# EN-C200-OPT_RA1.net
KiCad netlist of a schematic drawn in Altium Designer
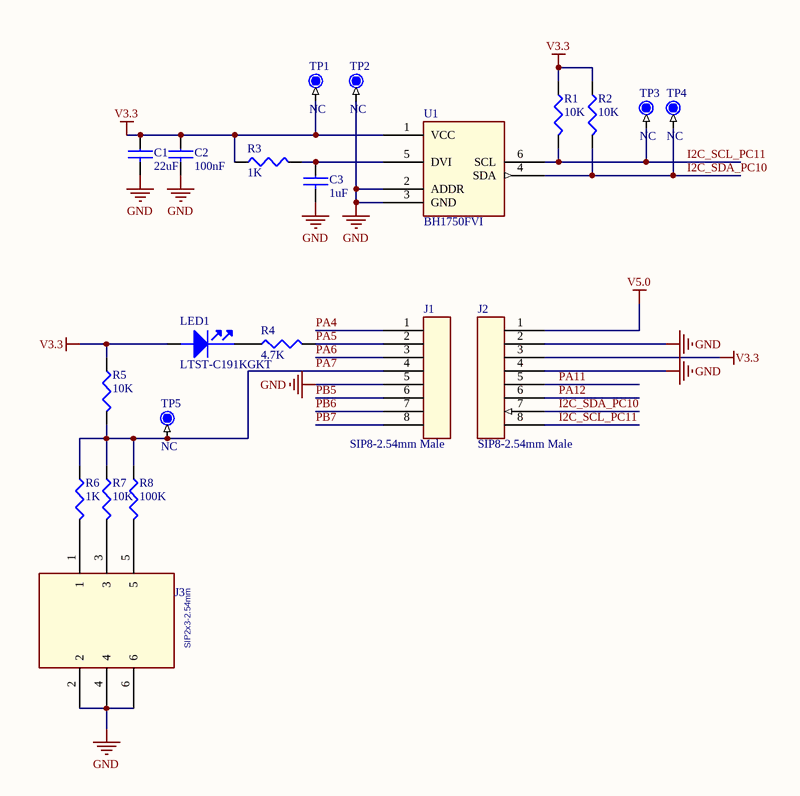
[diagram p0: EN-C200-OPT_RA1.SchDoc]

(export (version "E")
  (design (tool "Eeschema 10.0.6"))
  (components
    (comp (ref "C1")
      (value "22uF")
      (footprint "SC0805")
      (description "Y5V-10V/-25℃～+85℃/(-20%～+80%)")
      (libsource (lib "EN-C200-OPT") (part "CAP NP"))
    )
    (comp (ref "C2")
      (value "100nF")
      (footprint "SC0603")
      (description "X5R-50V/-55℃～+85℃/(±10%)")
      (libsource (lib "EN-C200-OPT") (part "CAP NP"))
    )
    (comp (ref "C3")
      (value "1uF")
      (footprint "SC0603")
      (description "X5R-16V/-55℃～+85℃/(±10%)")
      (libsource (lib "EN-C200-OPT") (part "CAP NP"))
    )
    (comp (ref "J1")
      (value "SIP8-2.54mm Male")
      (footprint "SIP-8P-100")
      (description "8Pin 2.54mmæé-éé«10mm/-40âï½+105â")
      (libsource (lib "EN-C200-OPT") (part "HEADER8"))
    )
    (comp (ref "J2")
      (value "SIP8-2.54mm Male")
      (footprint "SIP-8P-100")
      (description "8Pin 2.54mmæé-éé«10mm/-40âï½+105â")
      (libsource (lib "") (part "HEADER8_1"))
    )
    (comp (ref "J3")
      (value "SIP2x3-2.54mm")
      (footprint "SIP-2x3P-100")
      (description "2x3Pin 2.54mmæé-éé«10mm/-40âï½+105â")
      (libsource (lib "EN-C200-OPT") (part "CON2X3"))
    )
    (comp (ref "LED1")
      (value "LTST-C191KGKT")
      (footprint "HSD0603-LED")
      (description "绿色LED 2V-30mA/-55℃～+85℃")
      (libsource (lib "EN-C200-OPT") (part "LED"))
    )
    (comp (ref "R1")
      (value "10K")
      (footprint "SR0603")
      (description "碳膜-1/10W/-55℃～+155℃/5%")
      (libsource (lib "EN-C200-OPT") (part "RESISTOR"))
    )
    (comp (ref "R2")
      (value "10K")
      (footprint "SR0603")
      (description "碳膜-1/10W/-55℃～+155℃/5%")
      (libsource (lib "EN-C200-OPT") (part "RESISTOR"))
    )
    (comp (ref "R3")
      (value "1K")
      (footprint "SR0603")
      (description "碳膜-1/10W/-55℃～+155℃/5%")
      (libsource (lib "EN-C200-OPT") (part "RESISTOR"))
    )
    (comp (ref "R4")
      (value "4.7K")
      (footprint "SR0603")
      (description "碳膜-1/10W/-55℃～+155℃/5%")
      (libsource (lib "EN-C200-OPT") (part "RESISTOR"))
    )
    (comp (ref "R5")
      (value "10K")
      (footprint "SR0603")
      (description "碳膜-1/10W/-55℃～+155℃/5%")
      (libsource (lib "EN-C200-OPT") (part "RESISTOR"))
    )
    (comp (ref "R6")
      (value "1K")
      (footprint "SR0603")
      (description "碳膜-1/10W/-55℃～+155℃/5%")
      (libsource (lib "EN-C200-OPT") (part "RESISTOR"))
    )
    (comp (ref "R7")
      (value "10K")
      (footprint "SR0603")
      (description "碳膜-1/10W/-55℃～+155℃/5%")
      (libsource (lib "EN-C200-OPT") (part "RESISTOR"))
    )
    (comp (ref "R8")
      (value "100K")
      (footprint "SR0603")
      (description "碳膜-1/10W/-55℃～+155℃/5%")
      (libsource (lib "EN-C200-OPT") (part "RESISTOR"))
    )
    (comp (ref "TP1")
      (value "NC")
      (footprint "TP32-SMD")
      (description "0.8MM焊盘")
      (libsource (lib "EN-C200-OPT") (part "TP"))
    )
    (comp (ref "TP2")
      (value "NC")
      (footprint "TP32-SMD")
      (description "0.8MM焊盘")
      (libsource (lib "EN-C200-OPT") (part "TP"))
    )
    (comp (ref "TP3")
      (value "NC")
      (footprint "TP32-SMD")
      (description "0.8MM焊盘")
      (libsource (lib "EN-C200-OPT") (part "TP"))
    )
    (comp (ref "TP4")
      (value "NC")
      (footprint "TP32-SMD")
      (description "0.8MM焊盘")
      (libsource (lib "EN-C200-OPT") (part "TP"))
    )
    (comp (ref "TP5")
      (value "NC")
      (footprint "TP32-SMD")
      (description "0.8MM焊盘")
      (libsource (lib "EN-C200-OPT") (part "TP"))
    )
    (comp (ref "U1")
      (value "BH1750FVI")
      (footprint "sop6-20-105")
      (description "16ä½æ°å­è¾åºåç¯å¢åå¼ºåº¦ä¼ æå¨ï¼I2C BUS/-40â+85â")
      (libsource (lib "EN-C200-OPT") (part "BH1750HVI"))
    )
  )
  (nets
    (net (code "1") (name "/I2C_SCL_PC11") (class "Default")
      (node (ref "J2") (pin "8") (pinfunction "8_8") (pintype "passive"))
      (node (ref "R1") (pin "2") (pinfunction "2_2") (pintype "passive"))
      (node (ref "TP3") (pin "1") (pinfunction "1_1") (pintype "input"))
      (node (ref "U1") (pin "6") (pinfunction "SCL_6") (pintype "passive"))
    )
    (net (code "2") (name "/I2C_SDA_PC10") (class "Default")
      (node (ref "J2") (pin "7") (pinfunction "7_7") (pintype "input"))
      (node (ref "R2") (pin "2") (pinfunction "2_2") (pintype "passive"))
      (node (ref "TP4") (pin "1") (pinfunction "1_1") (pintype "input"))
      (node (ref "U1") (pin "4") (pinfunction "SDA_4") (pintype "output"))
    )
    (net (code "3") (name "/PA4") (class "Default")
      (node (ref "J1") (pin "1") (pinfunction "1_1") (pintype "passive"))
    )
    (net (code "4") (name "/PA5") (class "Default")
      (node (ref "J1") (pin "2") (pinfunction "2_2") (pintype "passive"))
      (node (ref "R4") (pin "2") (pinfunction "2_2") (pintype "passive"))
    )
    (net (code "5") (name "/PA6") (class "Default")
      (node (ref "J1") (pin "3") (pinfunction "3_3") (pintype "passive"))
    )
    (net (code "6") (name "/PA7") (class "Default")
      (node (ref "J1") (pin "4") (pinfunction "4_4") (pintype "passive"))
      (node (ref "R5") (pin "2") (pinfunction "2_2") (pintype "passive"))
      (node (ref "R6") (pin "1") (pinfunction "1_1") (pintype "passive"))
      (node (ref "R7") (pin "1") (pinfunction "1_1") (pintype "passive"))
      (node (ref "R8") (pin "1") (pinfunction "1_1") (pintype "passive"))
      (node (ref "TP5") (pin "1") (pinfunction "1_1") (pintype "input"))
    )
    (net (code "7") (name "/PA11") (class "Default")
      (node (ref "J2") (pin "5") (pinfunction "5_5") (pintype "passive"))
    )
    (net (code "8") (name "/PA12") (class "Default")
      (node (ref "J2") (pin "6") (pinfunction "6_6") (pintype "passive"))
    )
    (net (code "9") (name "/PB5") (class "Default")
      (node (ref "J1") (pin "6") (pinfunction "6_6") (pintype "passive"))
    )
    (net (code "10") (name "/PB6") (class "Default")
      (node (ref "J1") (pin "7") (pinfunction "7_7") (pintype "passive"))
    )
    (net (code "11") (name "/PB7") (class "Default")
      (node (ref "J1") (pin "8") (pinfunction "8_8") (pintype "passive"))
    )
    (net (code "12") (name "GND") (class "Default")
      (node (ref "C1") (pin "2") (pinfunction "2_2") (pintype "passive"))
      (node (ref "C2") (pin "2") (pinfunction "2_2") (pintype "passive"))
      (node (ref "C3") (pin "2") (pinfunction "2_2") (pintype "passive"))
      (node (ref "J1") (pin "5") (pinfunction "5_5") (pintype "passive"))
      (node (ref "J2") (pin "2") (pinfunction "2_2") (pintype "passive"))
      (node (ref "J2") (pin "4") (pinfunction "4_4") (pintype "passive"))
      (node (ref "J3") (pin "2") (pinfunction "2_2") (pintype "passive"))
      (node (ref "J3") (pin "4") (pinfunction "4_4") (pintype "passive"))
      (node (ref "J3") (pin "6") (pinfunction "6_6") (pintype "passive"))
      (node (ref "TP2") (pin "1") (pinfunction "1_1") (pintype "input"))
      (node (ref "U1") (pin "2") (pinfunction "ADDR_2") (pintype "passive"))
      (node (ref "U1") (pin "3") (pinfunction "GND_3") (pintype "passive"))
    )
    (net (code "13") (name "Net-(J3-Pad1)") (class "Default")
      (node (ref "J3") (pin "1") (pinfunction "1_1") (pintype "passive"))
      (node (ref "R6") (pin "2") (pinfunction "2_2") (pintype "passive"))
    )
    (net (code "14") (name "Net-(J3-Pad3)") (class "Default")
      (node (ref "J3") (pin "3") (pinfunction "3_3") (pintype "passive"))
      (node (ref "R7") (pin "2") (pinfunction "2_2") (pintype "passive"))
    )
    (net (code "15") (name "Net-(J3-Pad5)") (class "Default")
      (node (ref "J3") (pin "5") (pinfunction "5_5") (pintype "passive"))
      (node (ref "R8") (pin "2") (pinfunction "2_2") (pintype "passive"))
    )
    (net (code "16") (name "Net-(LED1-Pad2)") (class "Default")
      (node (ref "LED1") (pin "2") (pinfunction "2_2") (pintype "passive"))
      (node (ref "R4") (pin "1") (pinfunction "1_1") (pintype "passive"))
    )
    (net (code "17") (name "Net-(U1-DVI)") (class "Default")
      (node (ref "C3") (pin "1") (pinfunction "1_1") (pintype "passive"))
      (node (ref "R3") (pin "2") (pinfunction "2_2") (pintype "passive"))
      (node (ref "U1") (pin "5") (pinfunction "DVI_5") (pintype "passive"))
    )
    (net (code "18") (name "V3.3") (class "Default")
      (node (ref "C1") (pin "1") (pinfunction "1_1") (pintype "passive"))
      (node (ref "C2") (pin "1") (pinfunction "1_1") (pintype "passive"))
      (node (ref "J2") (pin "3") (pinfunction "3_3") (pintype "passive"))
      (node (ref "LED1") (pin "1") (pinfunction "1_1") (pintype "passive"))
      (node (ref "R1") (pin "1") (pinfunction "1_1") (pintype "passive"))
      (node (ref "R2") (pin "1") (pinfunction "1_1") (pintype "passive"))
      (node (ref "R3") (pin "1") (pinfunction "1_1") (pintype "passive"))
      (node (ref "R5") (pin "1") (pinfunction "1_1") (pintype "passive"))
      (node (ref "TP1") (pin "1") (pinfunction "1_1") (pintype "input"))
      (node (ref "U1") (pin "1") (pinfunction "VCC_1") (pintype "passive"))
    )
    (net (code "19") (name "V5.0") (class "Default")
      (node (ref "J2") (pin "1") (pinfunction "1_1") (pintype "passive"))
    )
  )
)
